# ETRX_FECU.net
KiCad netlist of a schematic drawn in Altium Designer
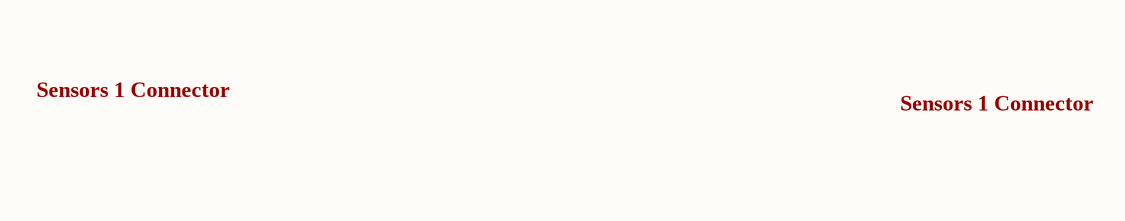
[diagram p0: ETRX_FECU.SchDoc, left]
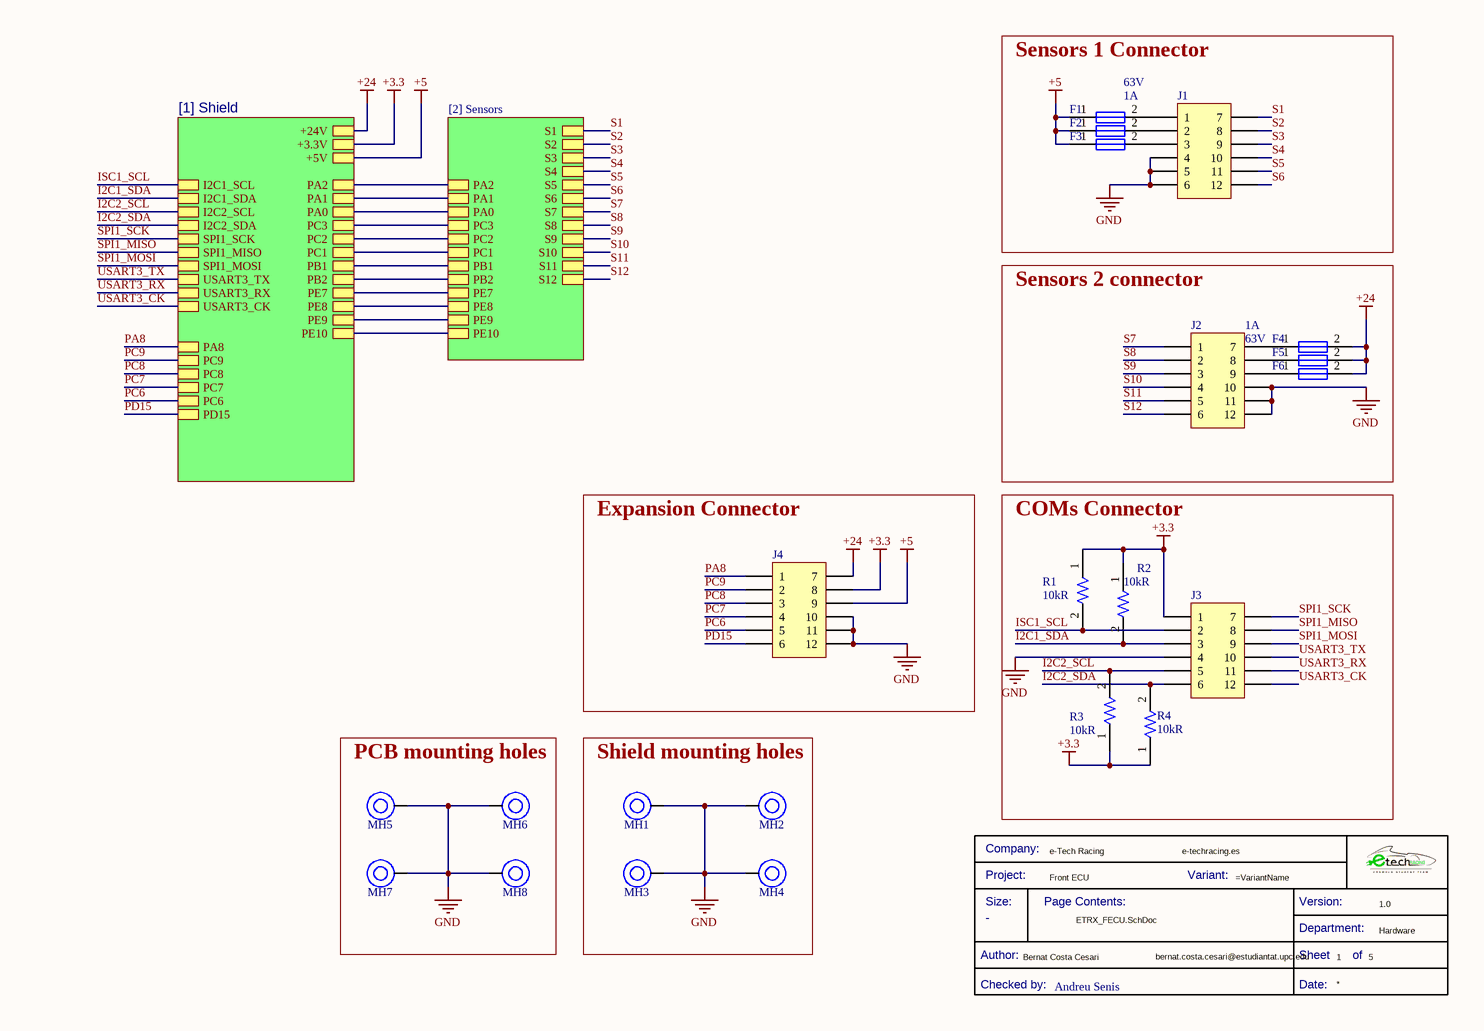
[diagram p1: ETRX_FECU.SchDoc, right]

(export (version "E")
  (design (tool "Eeschema 10.0.6"))
  (components
    (comp (ref "F1")
      (value "0437001.WRA")
      (footprint "Fuse_1206")
      (description "Fuse Chip Fast Acting 1A 63V SMD Solder Pad 1206 Ceramic T/R Automotive")
      (fields
        (field (name "MANUFACTURER") "Littelfuse")
        (field (name "CURRENT RATING") "1A")
        (field (name "VOLTAGE RATING (DC)") "63V")
        (field (name ".CREATOR") "DO")
      )
      (libsource (lib "Filter components") (part "Fuse_1A_63V_1206"))
    )
    (comp (ref "F2")
      (value "0437001.WRA")
      (footprint "Fuse_1206")
      (description "Fuse Chip Fast Acting 1A 63V SMD Solder Pad 1206 Ceramic T/R Automotive")
      (fields (field (name "MANUFACTURER") "Littelfuse") (field (name ".CREATOR") "DO"))
      (libsource (lib "Filter components") (part "Fuse_1A_63V_1206"))
    )
    (comp (ref "F3")
      (value "0437001.WRA")
      (footprint "Fuse_1206")
      (description "Fuse Chip Fast Acting 1A 63V SMD Solder Pad 1206 Ceramic T/R Automotive")
      (fields (field (name "MANUFACTURER") "Littelfuse") (field (name ".CREATOR") "DO"))
      (libsource (lib "Filter components") (part "Fuse_1A_63V_1206"))
    )
    (comp (ref "F4")
      (value "0437001.WRA")
      (footprint "Fuse_1206")
      (description "Fuse Chip Fast Acting 1A 63V SMD Solder Pad 1206 Ceramic T/R Automotive")
      (fields
        (field (name "MANUFACTURER") "Littelfuse")
        (field (name "CURRENT RATING") "1A")
        (field (name "VOLTAGE RATING (DC)") "63V")
        (field (name ".CREATOR") "DO")
      )
      (libsource (lib "Filter components") (part "Fuse_1A_63V_1206"))
    )
    (comp (ref "F5")
      (value "0437001.WRA")
      (footprint "Fuse_1206")
      (description "Fuse Chip Fast Acting 1A 63V SMD Solder Pad 1206 Ceramic T/R Automotive")
      (fields (field (name "MANUFACTURER") "Littelfuse") (field (name ".CREATOR") "DO"))
      (libsource (lib "Filter components") (part "Fuse_1A_63V_1206"))
    )
    (comp (ref "F6")
      (value "0437001.WRA")
      (footprint "Fuse_1206")
      (description "Fuse Chip Fast Acting 1A 63V SMD Solder Pad 1206 Ceramic T/R Automotive")
      (fields (field (name "MANUFACTURER") "Littelfuse") (field (name ".CREATOR") "DO"))
      (libsource (lib "Filter components") (part "Fuse_1A_63V_1206"))
    )
    (comp (ref "J1")
      (value "1053101112")
      (footprint "J_NanoFit_2x6_V")
      (libsource (lib "Electromechanical") (part "J_NanoFit_2x6_V"))
    )
    (comp (ref "J2")
      (value "1053101112")
      (footprint "J_NanoFit_2x6_V")
      (libsource (lib "Electromechanical") (part "J_NanoFit_2x6_V"))
    )
    (comp (ref "J3")
      (value "1053101112")
      (footprint "J_NanoFit_2x6_V")
      (libsource (lib "Electromechanical") (part "J_NanoFit_2x6_V"))
    )
    (comp (ref "J4")
      (value "1053101112")
      (footprint "J_NanoFit_2x6_V")
      (libsource (lib "Electromechanical") (part "J_NanoFit_2x6_V"))
    )
    (comp (ref "MH1")
      (value "Mounting_Hole_M3")
      (footprint "Mounting_Hole_M3")
      (libsource (lib "Electromechanical") (part "Mounting_Hole_M3"))
    )
    (comp (ref "MH2")
      (value "Mounting_Hole_M3")
      (footprint "Mounting_Hole_M3")
      (libsource (lib "Electromechanical") (part "Mounting_Hole_M3"))
    )
    (comp (ref "MH3")
      (value "Mounting_Hole_M3")
      (footprint "Mounting_Hole_M3")
      (libsource (lib "Electromechanical") (part "Mounting_Hole_M3"))
    )
    (comp (ref "MH4")
      (value "Mounting_Hole_M3")
      (footprint "Mounting_Hole_M3")
      (libsource (lib "Electromechanical") (part "Mounting_Hole_M3"))
    )
    (comp (ref "MH5")
      (value "Mounting_Hole_M4")
      (footprint "Mounting_Hole_M4")
      (libsource (lib "Electromechanical") (part "Mounting_Hole_M4"))
    )
    (comp (ref "MH6")
      (value "Mounting_Hole_M4")
      (footprint "Mounting_Hole_M4")
      (libsource (lib "Electromechanical") (part "Mounting_Hole_M4"))
    )
    (comp (ref "MH7")
      (value "Mounting_Hole_M4")
      (footprint "Mounting_Hole_M4")
      (libsource (lib "Electromechanical") (part "Mounting_Hole_M4"))
    )
    (comp (ref "MH8")
      (value "Mounting_Hole_M4")
      (footprint "Mounting_Hole_M4")
      (libsource (lib "Electromechanical") (part "Mounting_Hole_M4"))
    )
    (comp (ref "R1")
      (value "CR0805-JW-103ELF")
      (footprint "R0805FTK")
      (fields
        (field (name "TOLERANCE") "5%")
        (field (name "RESISTANCE") "10kR")
        (field (name ".CREATOR") "DR")
      )
      (libsource (lib "Passives") (part "R10k-0805FTK"))
    )
    (comp (ref "R2")
      (value "CR0805-JW-103ELF")
      (footprint "R0805FTK")
      (fields
        (field (name "TOLERANCE") "5%")
        (field (name "RESISTANCE") "10kR")
        (field (name ".CREATOR") "DR")
      )
      (libsource (lib "Passives") (part "R10k-0805FTK"))
    )
    (comp (ref "R3")
      (value "CR0805-JW-103ELF")
      (footprint "R0805FTK")
      (fields
        (field (name "TOLERANCE") "5%")
        (field (name "RESISTANCE") "10kR")
        (field (name ".CREATOR") "DR")
      )
      (libsource (lib "Passives") (part "R10k-0805FTK"))
    )
    (comp (ref "R4")
      (value "CR0805-JW-103ELF")
      (footprint "R0805FTK")
      (fields
        (field (name "TOLERANCE") "5%")
        (field (name "RESISTANCE") "10kR")
        (field (name ".CREATOR") "DR")
      )
      (libsource (lib "Passives") (part "R10k-0805FTK"))
    )
  )
  (nets
    (net (code "1") (name "+3.3") (class "Default")
      (node (ref "J3") (pin "1") (pinfunction "1_1") (pintype "passive"))
      (node (ref "J4") (pin "8") (pinfunction "8_8") (pintype "passive"))
      (node (ref "R1") (pin "1") (pinfunction "1_1") (pintype "passive"))
      (node (ref "R2") (pin "1") (pinfunction "1_1") (pintype "passive"))
      (node (ref "R3") (pin "1") (pinfunction "1_1") (pintype "passive"))
      (node (ref "R4") (pin "1") (pinfunction "1_1") (pintype "passive"))
    )
    (net (code "2") (name "+5") (class "Default")
      (node (ref "F1") (pin "1") (pinfunction "1_1") (pintype "passive"))
      (node (ref "F2") (pin "1") (pinfunction "1_1") (pintype "passive"))
      (node (ref "F3") (pin "1") (pinfunction "1_1") (pintype "passive"))
      (node (ref "J4") (pin "9") (pinfunction "9_9") (pintype "passive"))
    )
    (net (code "3") (name "+24") (class "Default")
      (node (ref "F4") (pin "2") (pinfunction "2_2") (pintype "passive"))
      (node (ref "F5") (pin "2") (pinfunction "2_2") (pintype "passive"))
      (node (ref "F6") (pin "2") (pinfunction "2_2") (pintype "passive"))
      (node (ref "J4") (pin "7") (pinfunction "7_7") (pintype "passive"))
    )
    (net (code "4") (name "/I2C1_SDA") (class "Default")
      (node (ref "J3") (pin "3") (pinfunction "3_3") (pintype "passive"))
      (node (ref "R2") (pin "2") (pinfunction "2_2") (pintype "passive"))
    )
    (net (code "5") (name "/I2C2_SCL") (class "Default")
      (node (ref "J3") (pin "5") (pinfunction "5_5") (pintype "passive"))
      (node (ref "R3") (pin "2") (pinfunction "2_2") (pintype "passive"))
    )
    (net (code "6") (name "/I2C2_SDA") (class "Default")
      (node (ref "J3") (pin "6") (pinfunction "6_6") (pintype "passive"))
      (node (ref "R4") (pin "2") (pinfunction "2_2") (pintype "passive"))
    )
    (net (code "7") (name "/ISC1_SCL") (class "Default")
      (node (ref "J3") (pin "2") (pinfunction "2_2") (pintype "passive"))
      (node (ref "R1") (pin "2") (pinfunction "2_2") (pintype "passive"))
    )
    (net (code "11") (name "/PA8") (class "Default")
      (node (ref "J4") (pin "1") (pinfunction "1_1") (pintype "passive"))
    )
    (net (code "17") (name "/PC6") (class "Default")
      (node (ref "J4") (pin "5") (pinfunction "5_5") (pintype "passive"))
    )
    (net (code "18") (name "/PC7") (class "Default")
      (node (ref "J4") (pin "4") (pinfunction "4_4") (pintype "passive"))
    )
    (net (code "19") (name "/PC8") (class "Default")
      (node (ref "J4") (pin "3") (pinfunction "3_3") (pintype "passive"))
    )
    (net (code "20") (name "/PC9") (class "Default")
      (node (ref "J4") (pin "2") (pinfunction "2_2") (pintype "passive"))
    )
    (net (code "21") (name "/PD15") (class "Default")
      (node (ref "J4") (pin "6") (pinfunction "6_6") (pintype "passive"))
    )
    (net (code "26") (name "/S1") (class "Default")
      (node (ref "J1") (pin "7") (pinfunction "7_7") (pintype "passive"))
    )
    (net (code "27") (name "/S2") (class "Default")
      (node (ref "J1") (pin "8") (pinfunction "8_8") (pintype "passive"))
    )
    (net (code "28") (name "/S3") (class "Default")
      (node (ref "J1") (pin "9") (pinfunction "9_9") (pintype "passive"))
    )
    (net (code "29") (name "/S4") (class "Default")
      (node (ref "J1") (pin "10") (pinfunction "10_10") (pintype "passive"))
    )
    (net (code "30") (name "/S5") (class "Default")
      (node (ref "J1") (pin "11") (pinfunction "11_11") (pintype "passive"))
    )
    (net (code "31") (name "/S6") (class "Default")
      (node (ref "J1") (pin "12") (pinfunction "12_12") (pintype "passive"))
    )
    (net (code "32") (name "/S7") (class "Default")
      (node (ref "J2") (pin "1") (pinfunction "1_1") (pintype "passive"))
    )
    (net (code "33") (name "/S8") (class "Default")
      (node (ref "J2") (pin "2") (pinfunction "2_2") (pintype "passive"))
    )
    (net (code "34") (name "/S9") (class "Default")
      (node (ref "J2") (pin "3") (pinfunction "3_3") (pintype "passive"))
    )
    (net (code "35") (name "/S10") (class "Default")
      (node (ref "J2") (pin "4") (pinfunction "4_4") (pintype "passive"))
    )
    (net (code "36") (name "/S11") (class "Default")
      (node (ref "J2") (pin "5") (pinfunction "5_5") (pintype "passive"))
    )
    (net (code "37") (name "/S12") (class "Default")
      (node (ref "J2") (pin "6") (pinfunction "6_6") (pintype "passive"))
    )
    (net (code "38") (name "/SPI1_MISO") (class "Default")
      (node (ref "J3") (pin "8") (pinfunction "8_8") (pintype "passive"))
    )
    (net (code "39") (name "/SPI1_MOSI") (class "Default")
      (node (ref "J3") (pin "9") (pinfunction "9_9") (pintype "passive"))
    )
    (net (code "40") (name "/SPI1_SCK") (class "Default")
      (node (ref "J3") (pin "7") (pinfunction "7_7") (pintype "passive"))
    )
    (net (code "41") (name "/USART3_CK") (class "Default")
      (node (ref "J3") (pin "12") (pinfunction "12_12") (pintype "passive"))
    )
    (net (code "42") (name "/USART3_RX") (class "Default")
      (node (ref "J3") (pin "11") (pinfunction "11_11") (pintype "passive"))
    )
    (net (code "43") (name "/USART3_TX") (class "Default")
      (node (ref "J3") (pin "10") (pinfunction "10_10") (pintype "passive"))
    )
    (net (code "44") (name "GND") (class "Default")
      (node (ref "J1") (pin "4") (pinfunction "4_4") (pintype "passive"))
      (node (ref "J1") (pin "5") (pinfunction "5_5") (pintype "passive"))
      (node (ref "J1") (pin "6") (pinfunction "6_6") (pintype "passive"))
      (node (ref "J2") (pin "10") (pinfunction "10_10") (pintype "passive"))
      (node (ref "J2") (pin "11") (pinfunction "11_11") (pintype "passive"))
      (node (ref "J2") (pin "12") (pinfunction "12_12") (pintype "passive"))
      (node (ref "J3") (pin "4") (pinfunction "4_4") (pintype "passive"))
      (node (ref "J4") (pin "10") (pinfunction "10_10") (pintype "passive"))
      (node (ref "J4") (pin "11") (pinfunction "11_11") (pintype "passive"))
      (node (ref "J4") (pin "12") (pinfunction "12_12") (pintype "passive"))
      (node (ref "MH1") (pin "1") (pinfunction "1_1") (pintype "passive"))
      (node (ref "MH2") (pin "1") (pinfunction "1_1") (pintype "passive"))
      (node (ref "MH3") (pin "1") (pinfunction "1_1") (pintype "passive"))
      (node (ref "MH4") (pin "1") (pinfunction "1_1") (pintype "passive"))
      (node (ref "MH5") (pin "1") (pinfunction "1_1") (pintype "passive"))
      (node (ref "MH6") (pin "1") (pinfunction "1_1") (pintype "passive"))
      (node (ref "MH7") (pin "1") (pinfunction "1_1") (pintype "passive"))
      (node (ref "MH8") (pin "1") (pinfunction "1_1") (pintype "passive"))
    )
    (net (code "45") (name "Net-(F1-Pad2)") (class "Default")
      (node (ref "F1") (pin "2") (pinfunction "2_2") (pintype "passive"))
      (node (ref "J1") (pin "1") (pinfunction "1_1") (pintype "passive"))
    )
    (net (code "46") (name "Net-(F2-Pad2)") (class "Default")
      (node (ref "F2") (pin "2") (pinfunction "2_2") (pintype "passive"))
      (node (ref "J1") (pin "2") (pinfunction "2_2") (pintype "passive"))
    )
    (net (code "47") (name "Net-(F3-Pad2)") (class "Default")
      (node (ref "F3") (pin "2") (pinfunction "2_2") (pintype "passive"))
      (node (ref "J1") (pin "3") (pinfunction "3_3") (pintype "passive"))
    )
    (net (code "48") (name "Net-(F4-Pad1)") (class "Default")
      (node (ref "F4") (pin "1") (pinfunction "1_1") (pintype "passive"))
      (node (ref "J2") (pin "7") (pinfunction "7_7") (pintype "passive"))
    )
    (net (code "49") (name "Net-(F5-Pad1)") (class "Default")
      (node (ref "F5") (pin "1") (pinfunction "1_1") (pintype "passive"))
      (node (ref "J2") (pin "8") (pinfunction "8_8") (pintype "passive"))
    )
    (net (code "50") (name "Net-(F6-Pad1)") (class "Default")
      (node (ref "F6") (pin "1") (pinfunction "1_1") (pintype "passive"))
      (node (ref "J2") (pin "9") (pinfunction "9_9") (pintype "passive"))
    )
  )
)
